# switch_matrix_circuit.net
KiCad netlist of a schematic drawn in EAGLE
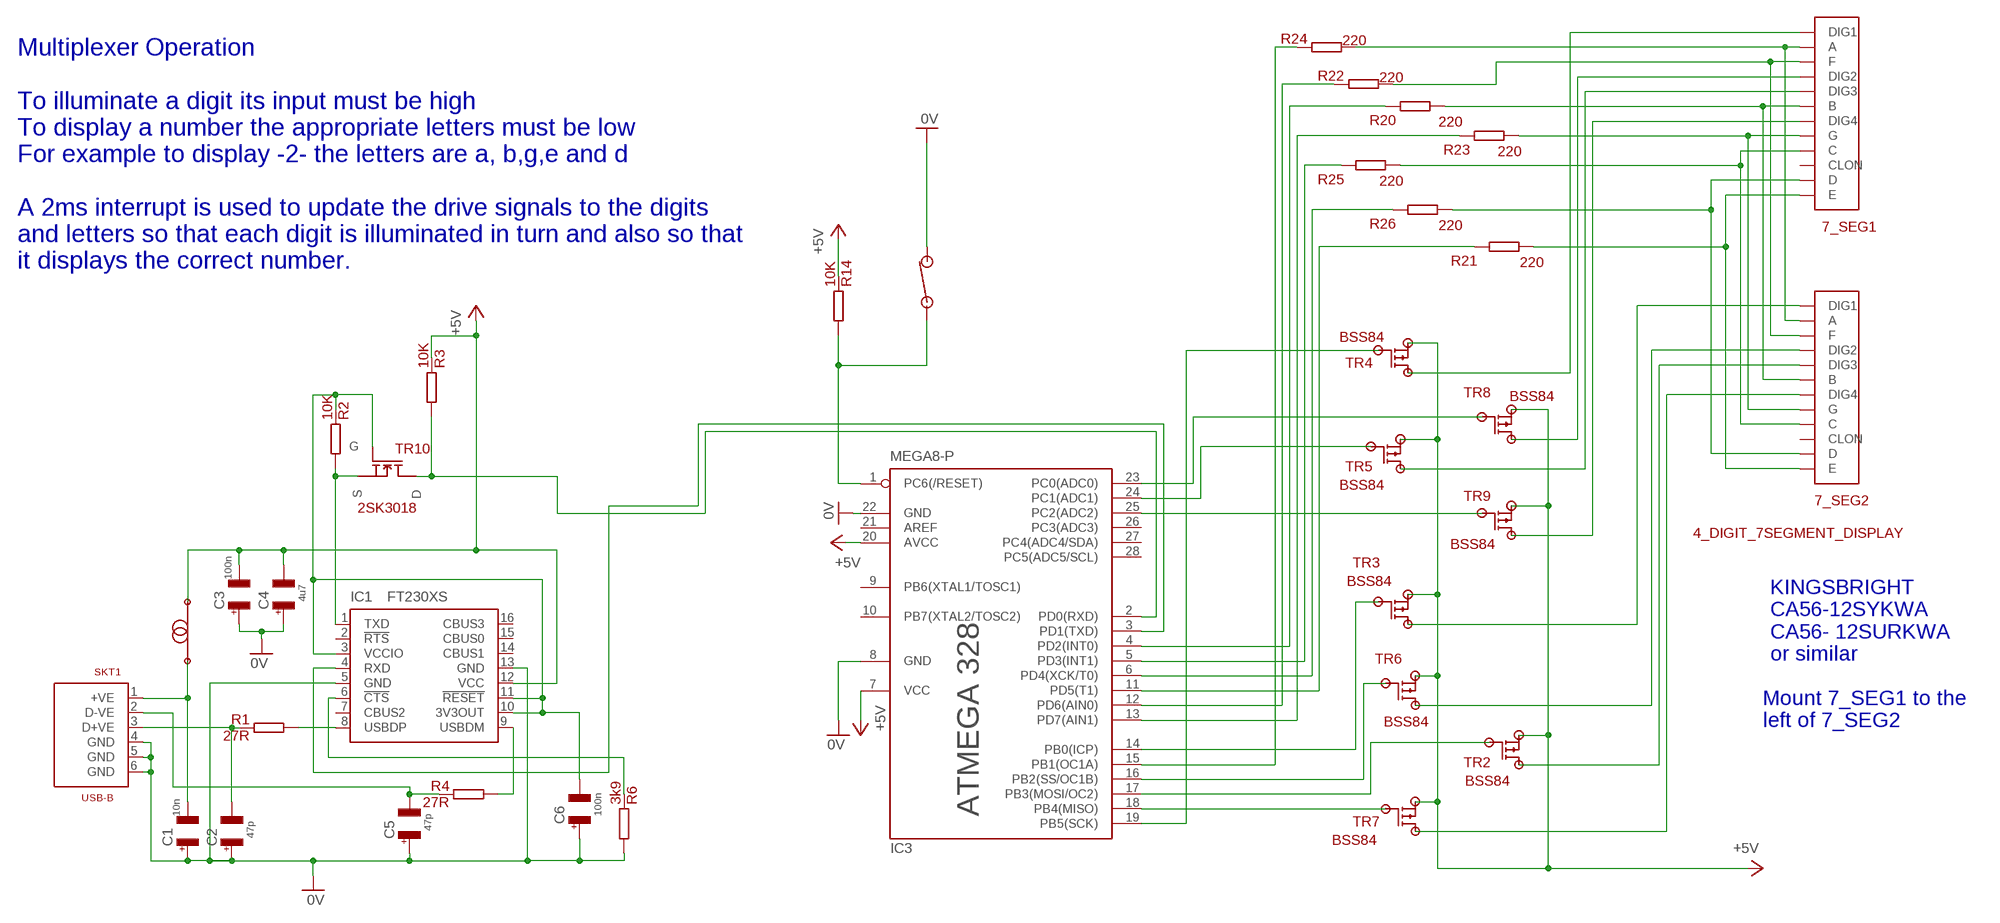
[diagram p0: schematic, sheet 1]

(export (version "E")
  (design (tool "Eeschema 10.0.6"))
  (components
    (comp (ref "7_SEG1")
      (value "4_DIGIT_7SEGMENT_DISPLAY")
      (footprint "eagle-import:4_DIGIT_7SEGMENT_DISPLAY")
      (libsource (lib "eagle-import") (part "4_DIGIT_7SEGMENT_DISPLAY"))
    )
    (comp (ref "7_SEG2")
      (value "4_DIGIT_7SEGMENT_DISPLAY")
      (footprint "eagle-import:4_DIGIT_7SEGMENT_DISPLAY")
      (libsource (lib "eagle-import") (part "4_DIGIT_7SEGMENT_DISPLAY"))
    )
    (comp (ref "C1")
      (value "10n")
      (footprint "eagle-import:1206")
      (libsource (lib "eagle-import") (part "1206C"))
    )
    (comp (ref "C2")
      (value "47p")
      (footprint "eagle-import:1206")
      (libsource (lib "eagle-import") (part "1206C"))
    )
    (comp (ref "C3")
      (value "100n")
      (footprint "eagle-import:1206")
      (libsource (lib "eagle-import") (part "1206C"))
    )
    (comp (ref "C4")
      (value "4u7")
      (footprint "eagle-import:1206")
      (libsource (lib "eagle-import") (part "1206C"))
    )
    (comp (ref "C5")
      (value "47p")
      (footprint "eagle-import:1206")
      (libsource (lib "eagle-import") (part "1206C"))
    )
    (comp (ref "C6")
      (value "100n")
      (footprint "eagle-import:1206")
      (libsource (lib "eagle-import") (part "1206C"))
    )
    (comp (ref "IC1")
      (value "FT230XS")
      (footprint "eagle-import:SSOP16")
      (libsource (lib "eagle-import") (part "FT230XS"))
    )
    (comp (ref "IC3")
      (value "MEGA8-P")
      (footprint "eagle-import:DIL28-3")
      (libsource (lib "eagle-import") (part "MEGA8-P"))
    )
    (comp (ref "L1")
      (value "CHOKE")
      (footprint "eagle-import:1206")
      (libsource (lib "eagle-import") (part "CHOKE"))
    )
    (comp (ref "R1")
      (value "27R")
      (footprint "eagle-import:1206")
      (libsource (lib "eagle-import") (part "1206R"))
    )
    (comp (ref "R2")
      (value "10K")
      (footprint "eagle-import:1206")
      (libsource (lib "eagle-import") (part "1206R"))
    )
    (comp (ref "R3")
      (value "10K")
      (footprint "eagle-import:1206")
      (libsource (lib "eagle-import") (part "1206R"))
    )
    (comp (ref "R4")
      (value "27R")
      (footprint "eagle-import:1206")
      (libsource (lib "eagle-import") (part "1206R"))
    )
    (comp (ref "R6")
      (value "3k9")
      (footprint "eagle-import:1206")
      (libsource (lib "eagle-import") (part "1206R"))
    )
    (comp (ref "R14")
      (value "10K")
      (footprint "eagle-import:1206")
      (libsource (lib "eagle-import") (part "1206R"))
    )
    (comp (ref "R20")
      (value "220")
      (footprint "eagle-import:1206")
      (libsource (lib "eagle-import") (part "1206R"))
    )
    (comp (ref "R21")
      (value "220")
      (footprint "eagle-import:1206")
      (libsource (lib "eagle-import") (part "1206R"))
    )
    (comp (ref "R22")
      (value "220")
      (footprint "eagle-import:1206")
      (libsource (lib "eagle-import") (part "1206R"))
    )
    (comp (ref "R23")
      (value "220")
      (footprint "eagle-import:1206")
      (libsource (lib "eagle-import") (part "1206R"))
    )
    (comp (ref "R24")
      (value "220")
      (footprint "eagle-import:1206")
      (libsource (lib "eagle-import") (part "1206R"))
    )
    (comp (ref "R25")
      (value "220")
      (footprint "eagle-import:1206")
      (libsource (lib "eagle-import") (part "1206R"))
    )
    (comp (ref "R26")
      (value "220")
      (footprint "eagle-import:1206")
      (libsource (lib "eagle-import") (part "1206R"))
    )
    (comp (ref "SKT1")
      (value "USB-B")
      (footprint "eagle-import:USB-B")
      (libsource (lib "eagle-import") (part "USB-B"))
    )
    (comp (ref "SW2")
      (value "NO_SW")
      (footprint "eagle-import:SM_NO_PUSH_BUTTON")
      (libsource (lib "eagle-import") (part "NO_SW"))
    )
    (comp (ref "TR2")
      (value "BSS84")
      (footprint "eagle-import:SOT23")
      (libsource (lib "eagle-import") (part "BSS84"))
    )
    (comp (ref "TR3")
      (value "BSS84")
      (footprint "eagle-import:SOT23")
      (libsource (lib "eagle-import") (part "BSS84"))
    )
    (comp (ref "TR4")
      (value "BSS84")
      (footprint "eagle-import:SOT23")
      (libsource (lib "eagle-import") (part "BSS84"))
    )
    (comp (ref "TR5")
      (value "BSS84")
      (footprint "eagle-import:SOT23")
      (libsource (lib "eagle-import") (part "BSS84"))
    )
    (comp (ref "TR6")
      (value "BSS84")
      (footprint "eagle-import:SOT23")
      (libsource (lib "eagle-import") (part "BSS84"))
    )
    (comp (ref "TR7")
      (value "BSS84")
      (footprint "eagle-import:SOT23")
      (libsource (lib "eagle-import") (part "BSS84"))
    )
    (comp (ref "TR8")
      (value "BSS84")
      (footprint "eagle-import:SOT23")
      (libsource (lib "eagle-import") (part "BSS84"))
    )
    (comp (ref "TR9")
      (value "BSS84")
      (footprint "eagle-import:SOT23")
      (libsource (lib "eagle-import") (part "BSS84"))
    )
    (comp (ref "TR10")
      (value "2SK3018")
      (footprint "eagle-import:2SK3018")
      (libsource (lib "eagle-import") (part "2SK3018"))
    )
  )
  (nets
    (net (code "1") (name "+5V") (class "Default")
      (node (ref "C3") (pin "P$2") (pinfunction "2_P$2") (pintype "bidirectional"))
      (node (ref "C4") (pin "P$2") (pinfunction "2_P$2") (pintype "bidirectional"))
      (node (ref "IC1") (pin "12") (pinfunction "VCC_12") (pintype "power_in"))
      (node (ref "IC3") (pin "20") (pinfunction "AVCC_20") (pintype "power_in"))
      (node (ref "IC3") (pin "7") (pinfunction "VCC_7") (pintype "power_in"))
      (node (ref "L1") (pin "P$2") (pinfunction "2_P$2") (pintype "bidirectional"))
      (node (ref "R14") (pin "P$2") (pinfunction "P$2_P$2") (pintype "bidirectional"))
      (node (ref "R3") (pin "P$2") (pinfunction "P$2_P$2") (pintype "bidirectional"))
      (node (ref "TR2") (pin "2") (pinfunction "S_2") (pintype "bidirectional"))
      (node (ref "TR3") (pin "2") (pinfunction "S_2") (pintype "bidirectional"))
      (node (ref "TR4") (pin "2") (pinfunction "S_2") (pintype "bidirectional"))
      (node (ref "TR5") (pin "2") (pinfunction "S_2") (pintype "bidirectional"))
      (node (ref "TR6") (pin "2") (pinfunction "S_2") (pintype "bidirectional"))
      (node (ref "TR7") (pin "2") (pinfunction "S_2") (pintype "bidirectional"))
      (node (ref "TR8") (pin "2") (pinfunction "S_2") (pintype "bidirectional"))
      (node (ref "TR9") (pin "2") (pinfunction "S_2") (pintype "bidirectional"))
    )
    (net (code "2") (name "0V") (class "Default")
      (node (ref "C1") (pin "P$1") (pinfunction "1_P$1") (pintype "bidirectional"))
      (node (ref "C2") (pin "P$1") (pinfunction "1_P$1") (pintype "bidirectional"))
      (node (ref "C3") (pin "P$1") (pinfunction "1_P$1") (pintype "bidirectional"))
      (node (ref "C4") (pin "P$1") (pinfunction "1_P$1") (pintype "bidirectional"))
      (node (ref "C5") (pin "P$1") (pinfunction "1_P$1") (pintype "bidirectional"))
      (node (ref "C6") (pin "P$1") (pinfunction "1_P$1") (pintype "bidirectional"))
      (node (ref "IC1") (pin "13") (pinfunction "GND_13") (pintype "power_in"))
      (node (ref "IC1") (pin "5") (pinfunction "GND_5") (pintype "power_in"))
      (node (ref "IC3") (pin "22") (pinfunction "GND_22") (pintype "power_in"))
      (node (ref "IC3") (pin "8") (pinfunction "GND_8") (pintype "power_in"))
      (node (ref "R6") (pin "P$1") (pinfunction "P$1_P$1") (pintype "bidirectional"))
      (node (ref "SKT1") (pin "4") (pinfunction "GND_4") (pintype "bidirectional"))
      (node (ref "SKT1") (pin "5") (pinfunction "GND_5") (pintype "bidirectional"))
      (node (ref "SKT1") (pin "6") (pinfunction "GND_6") (pintype "bidirectional"))
      (node (ref "SW2") (pin "P$2") (pinfunction "2_P$2") (pintype "bidirectional"))
    )
    (net (code "3") (name "Net-(7_SEG1-A)") (class "Default")
      (node (ref "7_SEG1") (pin "P$11") (pinfunction "A_P$11") (pintype "bidirectional"))
      (node (ref "7_SEG2") (pin "P$11") (pinfunction "A_P$11") (pintype "bidirectional"))
      (node (ref "R24") (pin "P$1") (pinfunction "P$1_P$1") (pintype "bidirectional"))
    )
    (net (code "4") (name "Net-(7_SEG1-B)") (class "Default")
      (node (ref "7_SEG1") (pin "P$7") (pinfunction "B_P$7") (pintype "bidirectional"))
      (node (ref "7_SEG2") (pin "P$7") (pinfunction "B_P$7") (pintype "bidirectional"))
      (node (ref "R20") (pin "P$1") (pinfunction "P$1_P$1") (pintype "bidirectional"))
    )
    (net (code "5") (name "Net-(7_SEG1-C)") (class "Default")
      (node (ref "7_SEG1") (pin "P$4") (pinfunction "C_P$4") (pintype "bidirectional"))
      (node (ref "7_SEG2") (pin "P$4") (pinfunction "C_P$4") (pintype "bidirectional"))
      (node (ref "R25") (pin "P$1") (pinfunction "P$1_P$1") (pintype "bidirectional"))
    )
    (net (code "6") (name "Net-(7_SEG1-D)") (class "Default")
      (node (ref "7_SEG1") (pin "P$2") (pinfunction "D_P$2") (pintype "bidirectional"))
      (node (ref "7_SEG2") (pin "P$2") (pinfunction "D_P$2") (pintype "bidirectional"))
      (node (ref "R26") (pin "P$1") (pinfunction "P$1_P$1") (pintype "bidirectional"))
    )
    (net (code "7") (name "Net-(7_SEG1-DIG1)") (class "Default")
      (node (ref "7_SEG1") (pin "P$12") (pinfunction "DIG1_P$12") (pintype "bidirectional"))
      (node (ref "TR4") (pin "3") (pinfunction "D_3") (pintype "bidirectional"))
    )
    (net (code "8") (name "Net-(7_SEG1-DIG2)") (class "Default")
      (node (ref "7_SEG1") (pin "P$9") (pinfunction "DIG2_P$9") (pintype "bidirectional"))
      (node (ref "TR8") (pin "3") (pinfunction "D_3") (pintype "bidirectional"))
    )
    (net (code "9") (name "Net-(7_SEG1-DIG3)") (class "Default")
      (node (ref "7_SEG1") (pin "P$8") (pinfunction "DIG3_P$8") (pintype "bidirectional"))
      (node (ref "TR5") (pin "3") (pinfunction "D_3") (pintype "bidirectional"))
    )
    (net (code "10") (name "Net-(7_SEG1-DIG4)") (class "Default")
      (node (ref "7_SEG1") (pin "P$6") (pinfunction "DIG4_P$6") (pintype "bidirectional"))
      (node (ref "TR9") (pin "3") (pinfunction "D_3") (pintype "bidirectional"))
    )
    (net (code "11") (name "Net-(7_SEG1-E)") (class "Default")
      (node (ref "7_SEG1") (pin "P$1") (pinfunction "E_P$1") (pintype "bidirectional"))
      (node (ref "7_SEG2") (pin "P$1") (pinfunction "E_P$1") (pintype "bidirectional"))
      (node (ref "R21") (pin "P$1") (pinfunction "P$1_P$1") (pintype "bidirectional"))
    )
    (net (code "12") (name "Net-(7_SEG1-F)") (class "Default")
      (node (ref "7_SEG1") (pin "P$10") (pinfunction "F_P$10") (pintype "bidirectional"))
      (node (ref "7_SEG2") (pin "P$10") (pinfunction "F_P$10") (pintype "bidirectional"))
      (node (ref "R22") (pin "P$1") (pinfunction "P$1_P$1") (pintype "bidirectional"))
    )
    (net (code "13") (name "Net-(7_SEG1-G)") (class "Default")
      (node (ref "7_SEG1") (pin "P$5") (pinfunction "G_P$5") (pintype "bidirectional"))
      (node (ref "7_SEG2") (pin "P$5") (pinfunction "G_P$5") (pintype "bidirectional"))
      (node (ref "R23") (pin "P$1") (pinfunction "P$1_P$1") (pintype "bidirectional"))
    )
    (net (code "14") (name "Net-(7_SEG2-DIG1)") (class "Default")
      (node (ref "7_SEG2") (pin "P$12") (pinfunction "DIG1_P$12") (pintype "bidirectional"))
      (node (ref "TR3") (pin "3") (pinfunction "D_3") (pintype "bidirectional"))
    )
    (net (code "15") (name "Net-(7_SEG2-DIG2)") (class "Default")
      (node (ref "7_SEG2") (pin "P$9") (pinfunction "DIG2_P$9") (pintype "bidirectional"))
      (node (ref "TR6") (pin "3") (pinfunction "D_3") (pintype "bidirectional"))
    )
    (net (code "16") (name "Net-(7_SEG2-DIG3)") (class "Default")
      (node (ref "7_SEG2") (pin "P$8") (pinfunction "DIG3_P$8") (pintype "bidirectional"))
      (node (ref "TR2") (pin "3") (pinfunction "D_3") (pintype "bidirectional"))
    )
    (net (code "17") (name "Net-(7_SEG2-DIG4)") (class "Default")
      (node (ref "7_SEG2") (pin "P$6") (pinfunction "DIG4_P$6") (pintype "bidirectional"))
      (node (ref "TR7") (pin "3") (pinfunction "D_3") (pintype "bidirectional"))
    )
    (net (code "18") (name "Net-(C1-2)") (class "Default")
      (node (ref "C1") (pin "P$2") (pinfunction "2_P$2") (pintype "bidirectional"))
      (node (ref "L1") (pin "P$1") (pinfunction "1_P$1") (pintype "bidirectional"))
      (node (ref "SKT1") (pin "1") (pinfunction "+VE_1") (pintype "bidirectional"))
    )
    (net (code "19") (name "Net-(C2-2)") (class "Default")
      (node (ref "C2") (pin "P$2") (pinfunction "2_P$2") (pintype "bidirectional"))
      (node (ref "R1") (pin "P$2") (pinfunction "P$2_P$2") (pintype "bidirectional"))
      (node (ref "SKT1") (pin "3") (pinfunction "D+VE_3") (pintype "bidirectional"))
    )
    (net (code "20") (name "Net-(C5-2)") (class "Default")
      (node (ref "C5") (pin "P$2") (pinfunction "2_P$2") (pintype "bidirectional"))
      (node (ref "R4") (pin "P$2") (pinfunction "P$2_P$2") (pintype "bidirectional"))
      (node (ref "SKT1") (pin "2") (pinfunction "D-VE_2") (pintype "bidirectional"))
    )
    (net (code "21") (name "Net-(C6-2)") (class "Default")
      (node (ref "C6") (pin "P$2") (pinfunction "2_P$2") (pintype "bidirectional"))
      (node (ref "IC1") (pin "10") (pinfunction "3V3OUT_10") (pintype "output"))
      (node (ref "IC1") (pin "11") (pinfunction "~{RESET}_11") (pintype "input"))
      (node (ref "IC1") (pin "3") (pinfunction "VCCIO_3") (pintype "power_in"))
      (node (ref "R2") (pin "P$2") (pinfunction "P$2_P$2") (pintype "bidirectional"))
      (node (ref "TR10") (pin "2") (pinfunction "G_2") (pintype "bidirectional"))
    )
    (net (code "22") (name "Net-(IC1-RXD)") (class "Default")
      (node (ref "IC1") (pin "4") (pinfunction "RXD_4") (pintype "input"))
      (node (ref "IC3") (pin "3") (pinfunction "PD1(TXD)_3") (pintype "bidirectional"))
    )
    (net (code "23") (name "Net-(IC1-TXD)") (class "Default")
      (node (ref "IC1") (pin "1") (pinfunction "TXD_1") (pintype "output"))
      (node (ref "R2") (pin "P$1") (pinfunction "P$1_P$1") (pintype "bidirectional"))
      (node (ref "TR10") (pin "1") (pinfunction "S_1") (pintype "bidirectional"))
    )
    (net (code "24") (name "Net-(IC1-USBDM)") (class "Default")
      (node (ref "IC1") (pin "9") (pinfunction "USBDM_9") (pintype "input"))
      (node (ref "R4") (pin "P$1") (pinfunction "P$1_P$1") (pintype "bidirectional"))
    )
    (net (code "25") (name "Net-(IC1-USBDP)") (class "Default")
      (node (ref "IC1") (pin "8") (pinfunction "USBDP_8") (pintype "input"))
      (node (ref "R1") (pin "P$1") (pinfunction "P$1_P$1") (pintype "bidirectional"))
    )
    (net (code "26") (name "Net-(IC1-~{CTS})") (class "Default")
      (node (ref "IC1") (pin "6") (pinfunction "~{CTS}_6") (pintype "input"))
      (node (ref "R6") (pin "P$2") (pinfunction "P$2_P$2") (pintype "bidirectional"))
    )
    (net (code "27") (name "Net-(IC3-PB0(ICP))") (class "Default")
      (node (ref "IC3") (pin "14") (pinfunction "PB0(ICP)_14") (pintype "bidirectional"))
      (node (ref "TR3") (pin "1") (pinfunction "G_1") (pintype "bidirectional"))
    )
    (net (code "28") (name "Net-(IC3-PB1(OC1A))") (class "Default")
      (node (ref "IC3") (pin "15") (pinfunction "PB1(OC1A)_15") (pintype "bidirectional"))
      (node (ref "R24") (pin "P$2") (pinfunction "P$2_P$2") (pintype "bidirectional"))
    )
    (net (code "29") (name "Net-(IC3-PB2(SS{slash}OC1B))") (class "Default")
      (node (ref "IC3") (pin "16") (pinfunction "PB2(SS/OC1B)_16") (pintype "bidirectional"))
      (node (ref "TR6") (pin "1") (pinfunction "G_1") (pintype "bidirectional"))
    )
    (net (code "30") (name "Net-(IC3-PB3(MOSI{slash}OC2))") (class "Default")
      (node (ref "IC3") (pin "17") (pinfunction "PB3(MOSI/OC2)_17") (pintype "bidirectional"))
      (node (ref "TR2") (pin "1") (pinfunction "G_1") (pintype "bidirectional"))
    )
    (net (code "31") (name "Net-(IC3-PB4(MISO))") (class "Default")
      (node (ref "IC3") (pin "18") (pinfunction "PB4(MISO)_18") (pintype "bidirectional"))
      (node (ref "TR7") (pin "1") (pinfunction "G_1") (pintype "bidirectional"))
    )
    (net (code "32") (name "Net-(IC3-PB5(SCK))") (class "Default")
      (node (ref "IC3") (pin "19") (pinfunction "PB5(SCK)_19") (pintype "bidirectional"))
      (node (ref "TR4") (pin "1") (pinfunction "G_1") (pintype "bidirectional"))
    )
    (net (code "33") (name "Net-(IC3-PC0(ADC0))") (class "Default")
      (node (ref "IC3") (pin "23") (pinfunction "PC0(ADC0)_23") (pintype "bidirectional"))
      (node (ref "TR8") (pin "1") (pinfunction "G_1") (pintype "bidirectional"))
    )
    (net (code "34") (name "Net-(IC3-PC1(ADC1))") (class "Default")
      (node (ref "IC3") (pin "24") (pinfunction "PC1(ADC1)_24") (pintype "bidirectional"))
      (node (ref "TR5") (pin "1") (pinfunction "G_1") (pintype "bidirectional"))
    )
    (net (code "35") (name "Net-(IC3-PC2(ADC2))") (class "Default")
      (node (ref "IC3") (pin "25") (pinfunction "PC2(ADC2)_25") (pintype "bidirectional"))
      (node (ref "TR9") (pin "1") (pinfunction "G_1") (pintype "bidirectional"))
    )
    (net (code "36") (name "Net-(IC3-PC6({slash}RESET))") (class "Default")
      (node (ref "IC3") (pin "1") (pinfunction "PC6(/RESET)_1") (pintype "bidirectional"))
      (node (ref "R14") (pin "P$1") (pinfunction "P$1_P$1") (pintype "bidirectional"))
      (node (ref "SW2") (pin "P$1") (pinfunction "1_P$1") (pintype "bidirectional"))
    )
    (net (code "37") (name "Net-(IC3-PD0(RXD))") (class "Default")
      (node (ref "IC3") (pin "2") (pinfunction "PD0(RXD)_2") (pintype "bidirectional"))
      (node (ref "R3") (pin "P$1") (pinfunction "P$1_P$1") (pintype "bidirectional"))
      (node (ref "TR10") (pin "3") (pinfunction "D_3") (pintype "bidirectional"))
    )
    (net (code "38") (name "Net-(IC3-PD2(INT0))") (class "Default")
      (node (ref "IC3") (pin "4") (pinfunction "PD2(INT0)_4") (pintype "bidirectional"))
      (node (ref "R20") (pin "P$2") (pinfunction "P$2_P$2") (pintype "bidirectional"))
    )
    (net (code "39") (name "Net-(IC3-PD3(INT1))") (class "Default")
      (node (ref "IC3") (pin "5") (pinfunction "PD3(INT1)_5") (pintype "bidirectional"))
      (node (ref "R25") (pin "P$2") (pinfunction "P$2_P$2") (pintype "bidirectional"))
    )
    (net (code "40") (name "Net-(IC3-PD4(XCK{slash}T0))") (class "Default")
      (node (ref "IC3") (pin "6") (pinfunction "PD4(XCK/T0)_6") (pintype "bidirectional"))
      (node (ref "R26") (pin "P$2") (pinfunction "P$2_P$2") (pintype "bidirectional"))
    )
    (net (code "41") (name "Net-(IC3-PD5(T1))") (class "Default")
      (node (ref "IC3") (pin "11") (pinfunction "PD5(T1)_11") (pintype "bidirectional"))
      (node (ref "R21") (pin "P$2") (pinfunction "P$2_P$2") (pintype "bidirectional"))
    )
    (net (code "42") (name "Net-(IC3-PD6(AIN0))") (class "Default")
      (node (ref "IC3") (pin "12") (pinfunction "PD6(AIN0)_12") (pintype "bidirectional"))
      (node (ref "R22") (pin "P$2") (pinfunction "P$2_P$2") (pintype "bidirectional"))
    )
    (net (code "43") (name "Net-(IC3-PD7(AIN1))") (class "Default")
      (node (ref "IC3") (pin "13") (pinfunction "PD7(AIN1)_13") (pintype "bidirectional"))
      (node (ref "R23") (pin "P$2") (pinfunction "P$2_P$2") (pintype "bidirectional"))
    )
    (net (code "44") (name "unconnected-(7_SEG1-CLON-PadP$3)") (class "Default")
      (node (ref "7_SEG1") (pin "P$3") (pinfunction "CLON_P$3") (pintype "bidirectional"))
    )
    (net (code "45") (name "unconnected-(7_SEG2-CLON-PadP$3)") (class "Default")
      (node (ref "7_SEG2") (pin "P$3") (pinfunction "CLON_P$3") (pintype "bidirectional"))
    )
    (net (code "46") (name "unconnected-(IC1-CBUS0-Pad15)") (class "Default")
      (node (ref "IC1") (pin "15") (pinfunction "CBUS0_15") (pintype "bidirectional"))
    )
    (net (code "47") (name "unconnected-(IC1-CBUS1-Pad14)") (class "Default")
      (node (ref "IC1") (pin "14") (pinfunction "CBUS1_14") (pintype "bidirectional"))
    )
    (net (code "48") (name "unconnected-(IC1-CBUS2-Pad7)") (class "Default")
      (node (ref "IC1") (pin "7") (pinfunction "CBUS2_7") (pintype "bidirectional"))
    )
    (net (code "49") (name "unconnected-(IC1-CBUS3-Pad16)") (class "Default")
      (node (ref "IC1") (pin "16") (pinfunction "CBUS3_16") (pintype "bidirectional"))
    )
    (net (code "50") (name "unconnected-(IC1-~{RTS}-Pad2)") (class "Default")
      (node (ref "IC1") (pin "2") (pinfunction "~{RTS}_2") (pintype "output"))
    )
    (net (code "51") (name "unconnected-(IC3-AREF-Pad21)") (class "Default")
      (node (ref "IC3") (pin "21") (pinfunction "AREF_21") (pintype "passive"))
    )
    (net (code "52") (name "unconnected-(IC3-PB6(XTAL1{slash}TOSC1)-Pad9)") (class "Default")
      (node (ref "IC3") (pin "9") (pinfunction "PB6(XTAL1/TOSC1)_9") (pintype "bidirectional"))
    )
    (net (code "53") (name "unconnected-(IC3-PB7(XTAL2{slash}TOSC2)-Pad10)") (class "Default")
      (node (ref "IC3") (pin "10") (pinfunction "PB7(XTAL2/TOSC2)_10") (pintype "bidirectional"))
    )
    (net (code "54") (name "unconnected-(IC3-PC3(ADC3)-Pad26)") (class "Default")
      (node (ref "IC3") (pin "26") (pinfunction "PC3(ADC3)_26") (pintype "bidirectional"))
    )
    (net (code "55") (name "unconnected-(IC3-PC4(ADC4{slash}SDA)-Pad27)") (class "Default")
      (node (ref "IC3") (pin "27") (pinfunction "PC4(ADC4/SDA)_27") (pintype "bidirectional"))
    )
    (net (code "56") (name "unconnected-(IC3-PC5(ADC5{slash}SCL)-Pad28)") (class "Default")
      (node (ref "IC3") (pin "28") (pinfunction "PC5(ADC5/SCL)_28") (pintype "bidirectional"))
    )
  )
)
